# Mako_DSP_Memory_R2_0_-_Copy.net
KiCad netlist of a schematic drawn in Altium Designer
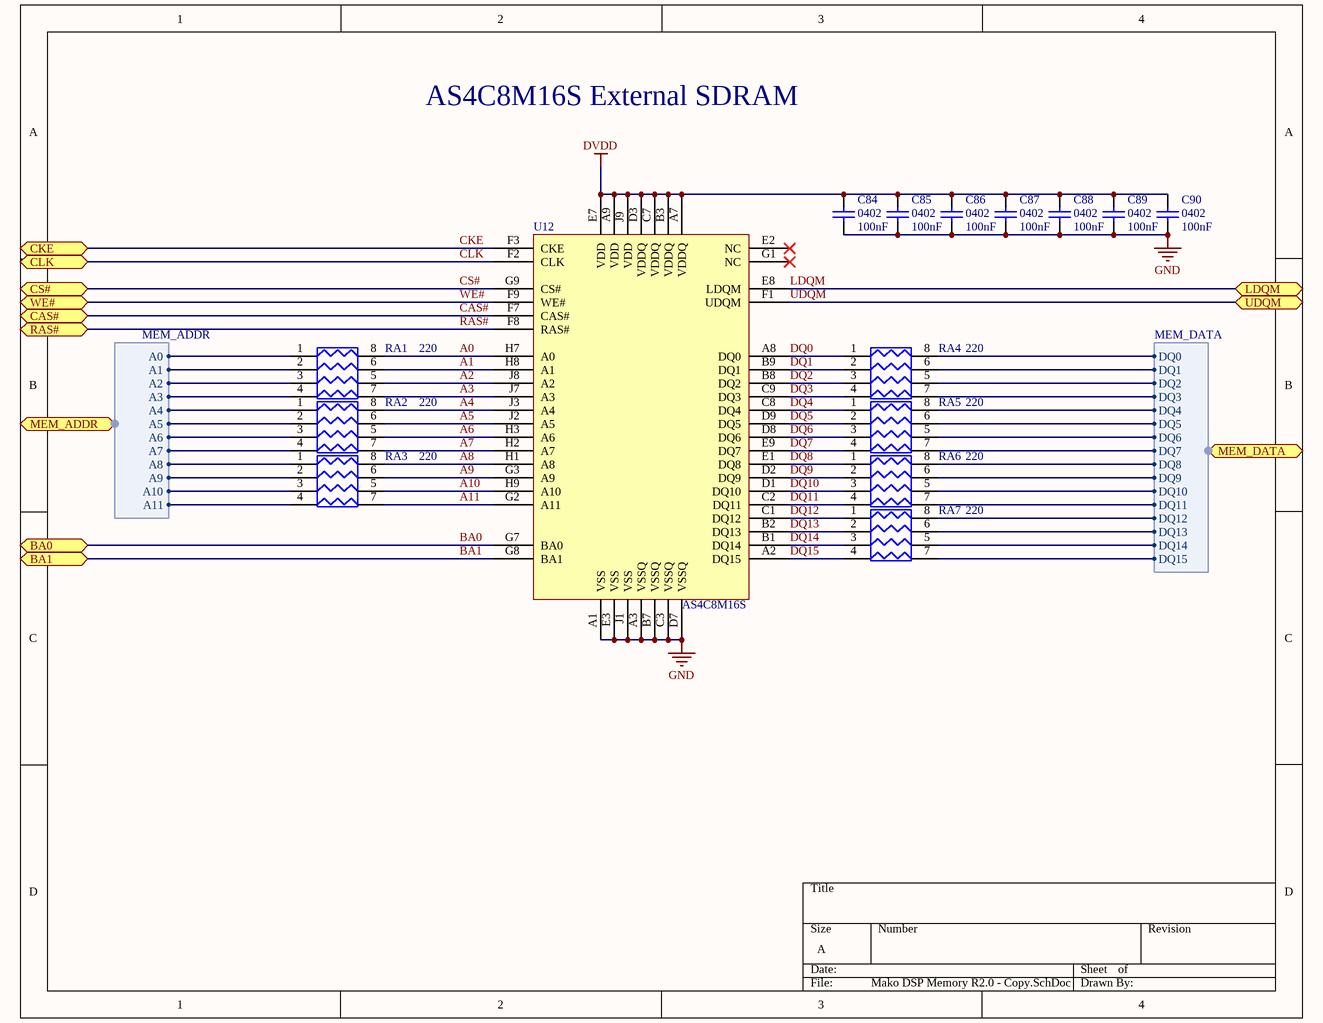
[diagram p0: Mako DSP Memory R2.0 - Copy.SchDoc]

(export (version "E")
  (design (tool "Eeschema 10.0.6"))
  (components
    (comp (ref "C84")
      (value "0402")
      (footprint "0402")
      (description "Capacitor (Semiconductor SIM Model)")
      (fields (field (name "ALTIUM_VALUE") "100nF") (field (name "PUBLISHER") "Altium Limited"))
      (libsource (lib "Miscellaneous Devices") (part "Cap Semi"))
    )
    (comp (ref "C85")
      (value "0402")
      (footprint "0402")
      (description "Capacitor (Semiconductor SIM Model)")
      (fields (field (name "ALTIUM_VALUE") "100nF") (field (name "PUBLISHER") "Altium Limited"))
      (libsource (lib "Miscellaneous Devices") (part "Cap Semi"))
    )
    (comp (ref "C86")
      (value "0402")
      (footprint "0402")
      (description "Capacitor (Semiconductor SIM Model)")
      (fields (field (name "ALTIUM_VALUE") "100nF") (field (name "PUBLISHER") "Altium Limited"))
      (libsource (lib "Miscellaneous Devices") (part "Cap Semi"))
    )
    (comp (ref "C87")
      (value "0402")
      (footprint "0402")
      (description "Capacitor (Semiconductor SIM Model)")
      (fields (field (name "ALTIUM_VALUE") "100nF") (field (name "PUBLISHER") "Altium Limited"))
      (libsource (lib "Miscellaneous Devices") (part "Cap Semi"))
    )
    (comp (ref "C88")
      (value "0402")
      (footprint "0402")
      (description "Capacitor (Semiconductor SIM Model)")
      (fields (field (name "ALTIUM_VALUE") "100nF") (field (name "PUBLISHER") "Altium Limited"))
      (libsource (lib "Miscellaneous Devices") (part "Cap Semi"))
    )
    (comp (ref "C89")
      (value "0402")
      (footprint "0402")
      (description "Capacitor (Semiconductor SIM Model)")
      (fields (field (name "ALTIUM_VALUE") "100nF") (field (name "PUBLISHER") "Altium Limited"))
      (libsource (lib "Miscellaneous Devices") (part "Cap Semi"))
    )
    (comp (ref "C90")
      (value "0402")
      (footprint "0402")
      (description "Capacitor (Semiconductor SIM Model)")
      (fields (field (name "ALTIUM_VALUE") "100nF") (field (name "PUBLISHER") "Altium Limited"))
      (libsource (lib "Miscellaneous Devices") (part "Cap Semi"))
    )
    (comp (ref "RA1")
      (value "220")
      (footprint "742C083")
      (description "Resistor array")
      (fields (field (name "Comment") "RESISTOR ARRAY"))
      (libsource (lib "Mako DSP Schematic Library") (part "RESISTOR ARRAY"))
    )
    (comp (ref "RA2")
      (value "220")
      (footprint "742C083")
      (description "Resistor array")
      (fields (field (name "Comment") "RESISTOR ARRAY"))
      (libsource (lib "Mako DSP Schematic Library") (part "RESISTOR ARRAY"))
    )
    (comp (ref "RA3")
      (value "220")
      (footprint "742C083")
      (description "Resistor array")
      (fields (field (name "Comment") "RESISTOR ARRAY"))
      (libsource (lib "Mako DSP Schematic Library") (part "RESISTOR ARRAY"))
    )
    (comp (ref "RA4")
      (value "220")
      (footprint "742C083")
      (description "Resistor array")
      (fields (field (name "Comment") "RESISTOR ARRAY"))
      (libsource (lib "Mako DSP Schematic Library") (part "RESISTOR ARRAY"))
    )
    (comp (ref "RA5")
      (value "220")
      (footprint "742C083")
      (description "Resistor array")
      (fields (field (name "Comment") "RESISTOR ARRAY"))
      (libsource (lib "Mako DSP Schematic Library") (part "RESISTOR ARRAY"))
    )
    (comp (ref "RA6")
      (value "220")
      (footprint "742C083")
      (description "Resistor array")
      (fields (field (name "Comment") "RESISTOR ARRAY"))
      (libsource (lib "Mako DSP Schematic Library") (part "RESISTOR ARRAY"))
    )
    (comp (ref "RA7")
      (value "220")
      (footprint "742C083")
      (description "Resistor array")
      (fields (field (name "Comment") "RESISTOR ARRAY"))
      (libsource (lib "Mako DSP Schematic Library") (part "RESISTOR ARRAY"))
    )
    (comp (ref "U12")
      (value "AS4C8M16S")
      (footprint "AS4C8M16S")
      (libsource (lib "Mako DSP Schematic Library") (part "AS4C8M16S"))
    )
  )
  (nets
    (net (code "3") (name "/A0") (class "Default")
      (node (ref "RA1") (pin "8") (pinfunction "8_8") (pintype "passive"))
      (node (ref "U12") (pin "H7") (pinfunction "A0_H7") (pintype "passive"))
    )
    (net (code "4") (name "/A1") (class "Default")
      (node (ref "RA1") (pin "6") (pinfunction "6_6") (pintype "passive"))
      (node (ref "U12") (pin "H8") (pinfunction "A1_H8") (pintype "passive"))
    )
    (net (code "5") (name "/A2") (class "Default")
      (node (ref "RA1") (pin "5") (pinfunction "5_5") (pintype "passive"))
      (node (ref "U12") (pin "J8") (pinfunction "A2_J8") (pintype "passive"))
    )
    (net (code "6") (name "/A3") (class "Default")
      (node (ref "RA1") (pin "7") (pinfunction "7_7") (pintype "passive"))
      (node (ref "U12") (pin "J7") (pinfunction "A3_J7") (pintype "passive"))
    )
    (net (code "7") (name "/A4") (class "Default")
      (node (ref "RA2") (pin "8") (pinfunction "8_8") (pintype "passive"))
      (node (ref "U12") (pin "J3") (pinfunction "A4_J3") (pintype "passive"))
    )
    (net (code "8") (name "/A5") (class "Default")
      (node (ref "RA2") (pin "6") (pinfunction "6_6") (pintype "passive"))
      (node (ref "U12") (pin "J2") (pinfunction "A5_J2") (pintype "passive"))
    )
    (net (code "9") (name "/A6") (class "Default")
      (node (ref "RA2") (pin "5") (pinfunction "5_5") (pintype "passive"))
      (node (ref "U12") (pin "H3") (pinfunction "A6_H3") (pintype "passive"))
    )
    (net (code "10") (name "/A7") (class "Default")
      (node (ref "RA2") (pin "7") (pinfunction "7_7") (pintype "passive"))
      (node (ref "U12") (pin "H2") (pinfunction "A7_H2") (pintype "passive"))
    )
    (net (code "11") (name "/A8") (class "Default")
      (node (ref "RA3") (pin "8") (pinfunction "8_8") (pintype "passive"))
      (node (ref "U12") (pin "H1") (pinfunction "A8_H1") (pintype "passive"))
    )
    (net (code "12") (name "/A9") (class "Default")
      (node (ref "RA3") (pin "6") (pinfunction "6_6") (pintype "passive"))
      (node (ref "U12") (pin "G3") (pinfunction "A9_G3") (pintype "passive"))
    )
    (net (code "13") (name "/A10") (class "Default")
      (node (ref "RA3") (pin "5") (pinfunction "5_5") (pintype "passive"))
      (node (ref "U12") (pin "H9") (pinfunction "A10_H9") (pintype "passive"))
    )
    (net (code "14") (name "/A11") (class "Default")
      (node (ref "RA3") (pin "7") (pinfunction "7_7") (pintype "passive"))
      (node (ref "U12") (pin "G2") (pinfunction "A11_G2") (pintype "passive"))
    )
    (net (code "15") (name "/BA0") (class "Default")
      (node (ref "U12") (pin "G7") (pinfunction "BA0_G7") (pintype "passive"))
    )
    (net (code "16") (name "/BA1") (class "Default")
      (node (ref "U12") (pin "G8") (pinfunction "BA1_G8") (pintype "passive"))
    )
    (net (code "17") (name "/CAS#") (class "Default")
      (node (ref "U12") (pin "F7") (pinfunction "CAS#_F7") (pintype "passive"))
    )
    (net (code "18") (name "/CKE") (class "Default")
      (node (ref "U12") (pin "F3") (pinfunction "CKE_F3") (pintype "passive"))
    )
    (net (code "19") (name "/CLK") (class "Default")
      (node (ref "U12") (pin "F2") (pinfunction "CLK_F2") (pintype "passive"))
    )
    (net (code "20") (name "/CS#") (class "Default")
      (node (ref "U12") (pin "G9") (pinfunction "CS#_G9") (pintype "passive"))
    )
    (net (code "21") (name "/DQ0") (class "Default")
      (node (ref "RA4") (pin "1") (pinfunction "1_1") (pintype "passive"))
      (node (ref "U12") (pin "A8") (pinfunction "DQ0_A8") (pintype "passive"))
    )
    (net (code "22") (name "/DQ1") (class "Default")
      (node (ref "RA4") (pin "2") (pinfunction "2_2") (pintype "passive"))
      (node (ref "U12") (pin "B9") (pinfunction "DQ1_B9") (pintype "passive"))
    )
    (net (code "23") (name "/DQ2") (class "Default")
      (node (ref "RA4") (pin "3") (pinfunction "3_3") (pintype "passive"))
      (node (ref "U12") (pin "B8") (pinfunction "DQ2_B8") (pintype "passive"))
    )
    (net (code "24") (name "/DQ3") (class "Default")
      (node (ref "RA4") (pin "4") (pinfunction "4_4") (pintype "passive"))
      (node (ref "U12") (pin "C9") (pinfunction "DQ3_C9") (pintype "passive"))
    )
    (net (code "25") (name "/DQ4") (class "Default")
      (node (ref "RA5") (pin "1") (pinfunction "1_1") (pintype "passive"))
      (node (ref "U12") (pin "C8") (pinfunction "DQ4_C8") (pintype "passive"))
    )
    (net (code "26") (name "/DQ5") (class "Default")
      (node (ref "RA5") (pin "2") (pinfunction "2_2") (pintype "passive"))
      (node (ref "U12") (pin "D9") (pinfunction "DQ5_D9") (pintype "passive"))
    )
    (net (code "27") (name "/DQ6") (class "Default")
      (node (ref "RA5") (pin "3") (pinfunction "3_3") (pintype "passive"))
      (node (ref "U12") (pin "D8") (pinfunction "DQ6_D8") (pintype "passive"))
    )
    (net (code "28") (name "/DQ7") (class "Default")
      (node (ref "RA5") (pin "4") (pinfunction "4_4") (pintype "passive"))
      (node (ref "U12") (pin "E9") (pinfunction "DQ7_E9") (pintype "passive"))
    )
    (net (code "29") (name "/DQ8") (class "Default")
      (node (ref "RA6") (pin "1") (pinfunction "1_1") (pintype "passive"))
      (node (ref "U12") (pin "E1") (pinfunction "DQ8_E1") (pintype "passive"))
    )
    (net (code "30") (name "/DQ9") (class "Default")
      (node (ref "RA6") (pin "2") (pinfunction "2_2") (pintype "passive"))
      (node (ref "U12") (pin "D2") (pinfunction "DQ9_D2") (pintype "passive"))
    )
    (net (code "31") (name "/DQ10") (class "Default")
      (node (ref "RA6") (pin "3") (pinfunction "3_3") (pintype "passive"))
      (node (ref "U12") (pin "D1") (pinfunction "DQ10_D1") (pintype "passive"))
    )
    (net (code "32") (name "/DQ11") (class "Default")
      (node (ref "RA6") (pin "4") (pinfunction "4_4") (pintype "passive"))
      (node (ref "U12") (pin "C2") (pinfunction "DQ11_C2") (pintype "passive"))
    )
    (net (code "33") (name "/DQ12") (class "Default")
      (node (ref "RA7") (pin "1") (pinfunction "1_1") (pintype "passive"))
      (node (ref "U12") (pin "C1") (pinfunction "DQ12_C1") (pintype "passive"))
    )
    (net (code "34") (name "/DQ13") (class "Default")
      (node (ref "RA7") (pin "2") (pinfunction "2_2") (pintype "passive"))
      (node (ref "U12") (pin "B2") (pinfunction "DQ13_B2") (pintype "passive"))
    )
    (net (code "35") (name "/DQ14") (class "Default")
      (node (ref "RA7") (pin "3") (pinfunction "3_3") (pintype "passive"))
      (node (ref "U12") (pin "B1") (pinfunction "DQ14_B1") (pintype "passive"))
    )
    (net (code "36") (name "/DQ15") (class "Default")
      (node (ref "RA7") (pin "4") (pinfunction "4_4") (pintype "passive"))
      (node (ref "U12") (pin "A2") (pinfunction "DQ15_A2") (pintype "passive"))
    )
    (net (code "37") (name "/LDQM") (class "Default")
      (node (ref "U12") (pin "E8") (pinfunction "LDQM_E8") (pintype "passive"))
    )
    (net (code "38") (name "/RAS#") (class "Default")
      (node (ref "U12") (pin "F8") (pinfunction "RAS#_F8") (pintype "passive"))
    )
    (net (code "39") (name "/UDQM") (class "Default")
      (node (ref "U12") (pin "F1") (pinfunction "UDQM_F1") (pintype "passive"))
    )
    (net (code "40") (name "/WE#") (class "Default")
      (node (ref "U12") (pin "F9") (pinfunction "WE#_F9") (pintype "passive"))
    )
    (net (code "43") (name "DVDD") (class "Default")
      (node (ref "C84") (pin "2") (pinfunction "2_2") (pintype "passive"))
      (node (ref "C85") (pin "2") (pinfunction "2_2") (pintype "passive"))
      (node (ref "C86") (pin "2") (pinfunction "2_2") (pintype "passive"))
      (node (ref "C87") (pin "2") (pinfunction "2_2") (pintype "passive"))
      (node (ref "C88") (pin "2") (pinfunction "2_2") (pintype "passive"))
      (node (ref "C89") (pin "2") (pinfunction "2_2") (pintype "passive"))
      (node (ref "C90") (pin "2") (pinfunction "2_2") (pintype "passive"))
      (node (ref "U12") (pin "A7") (pinfunction "VDDQ_A7") (pintype "passive"))
      (node (ref "U12") (pin "A9") (pinfunction "VDD_A9") (pintype "passive"))
      (node (ref "U12") (pin "B3") (pinfunction "VDDQ_B3") (pintype "passive"))
      (node (ref "U12") (pin "C7") (pinfunction "VDDQ_C7") (pintype "passive"))
      (node (ref "U12") (pin "D3") (pinfunction "VDDQ_D3") (pintype "passive"))
      (node (ref "U12") (pin "E7") (pinfunction "VDD_E7") (pintype "passive"))
      (node (ref "U12") (pin "J9") (pinfunction "VDD_J9") (pintype "passive"))
    )
    (net (code "44") (name "GND") (class "Default")
      (node (ref "C84") (pin "1") (pinfunction "1_1") (pintype "passive"))
      (node (ref "C85") (pin "1") (pinfunction "1_1") (pintype "passive"))
      (node (ref "C86") (pin "1") (pinfunction "1_1") (pintype "passive"))
      (node (ref "C87") (pin "1") (pinfunction "1_1") (pintype "passive"))
      (node (ref "C88") (pin "1") (pinfunction "1_1") (pintype "passive"))
      (node (ref "C89") (pin "1") (pinfunction "1_1") (pintype "passive"))
      (node (ref "C90") (pin "1") (pinfunction "1_1") (pintype "passive"))
      (node (ref "U12") (pin "A1") (pinfunction "VSS_A1") (pintype "passive"))
      (node (ref "U12") (pin "A3") (pinfunction "VSSQ_A3") (pintype "passive"))
      (node (ref "U12") (pin "B7") (pinfunction "VSSQ_B7") (pintype "passive"))
      (node (ref "U12") (pin "C3") (pinfunction "VSSQ_C3") (pintype "passive"))
      (node (ref "U12") (pin "D7") (pinfunction "VSSQ_D7") (pintype "passive"))
      (node (ref "U12") (pin "E3") (pinfunction "VSS_E3") (pintype "passive"))
      (node (ref "U12") (pin "J1") (pinfunction "VSS_J1") (pintype "passive"))
    )
    (net (code "45") (name "unconnected-(RA1-Pad1)") (class "Default")
      (node (ref "RA1") (pin "1") (pinfunction "1_1") (pintype "passive"))
    )
    (net (code "46") (name "unconnected-(RA1-Pad2)") (class "Default")
      (node (ref "RA1") (pin "2") (pinfunction "2_2") (pintype "passive"))
    )
    (net (code "47") (name "unconnected-(RA1-Pad3)") (class "Default")
      (node (ref "RA1") (pin "3") (pinfunction "3_3") (pintype "passive"))
    )
    (net (code "48") (name "unconnected-(RA1-Pad4)") (class "Default")
      (node (ref "RA1") (pin "4") (pinfunction "4_4") (pintype "passive"))
    )
    (net (code "49") (name "unconnected-(RA2-Pad1)") (class "Default")
      (node (ref "RA2") (pin "1") (pinfunction "1_1") (pintype "passive"))
    )
    (net (code "50") (name "unconnected-(RA2-Pad2)") (class "Default")
      (node (ref "RA2") (pin "2") (pinfunction "2_2") (pintype "passive"))
    )
    (net (code "51") (name "unconnected-(RA2-Pad3)") (class "Default")
      (node (ref "RA2") (pin "3") (pinfunction "3_3") (pintype "passive"))
    )
    (net (code "52") (name "unconnected-(RA2-Pad4)") (class "Default")
      (node (ref "RA2") (pin "4") (pinfunction "4_4") (pintype "passive"))
    )
    (net (code "53") (name "unconnected-(RA3-Pad1)") (class "Default")
      (node (ref "RA3") (pin "1") (pinfunction "1_1") (pintype "passive"))
    )
    (net (code "54") (name "unconnected-(RA3-Pad2)") (class "Default")
      (node (ref "RA3") (pin "2") (pinfunction "2_2") (pintype "passive"))
    )
    (net (code "55") (name "unconnected-(RA3-Pad3)") (class "Default")
      (node (ref "RA3") (pin "3") (pinfunction "3_3") (pintype "passive"))
    )
    (net (code "56") (name "unconnected-(RA3-Pad4)") (class "Default")
      (node (ref "RA3") (pin "4") (pinfunction "4_4") (pintype "passive"))
    )
    (net (code "57") (name "unconnected-(RA4-Pad5)") (class "Default")
      (node (ref "RA4") (pin "5") (pinfunction "5_5") (pintype "passive"))
    )
    (net (code "58") (name "unconnected-(RA4-Pad6)") (class "Default")
      (node (ref "RA4") (pin "6") (pinfunction "6_6") (pintype "passive"))
    )
    (net (code "59") (name "unconnected-(RA4-Pad7)") (class "Default")
      (node (ref "RA4") (pin "7") (pinfunction "7_7") (pintype "passive"))
    )
    (net (code "60") (name "unconnected-(RA4-Pad8)") (class "Default")
      (node (ref "RA4") (pin "8") (pinfunction "8_8") (pintype "passive"))
    )
    (net (code "61") (name "unconnected-(RA5-Pad5)") (class "Default")
      (node (ref "RA5") (pin "5") (pinfunction "5_5") (pintype "passive"))
    )
    (net (code "62") (name "unconnected-(RA5-Pad6)") (class "Default")
      (node (ref "RA5") (pin "6") (pinfunction "6_6") (pintype "passive"))
    )
    (net (code "63") (name "unconnected-(RA5-Pad7)") (class "Default")
      (node (ref "RA5") (pin "7") (pinfunction "7_7") (pintype "passive"))
    )
    (net (code "64") (name "unconnected-(RA5-Pad8)") (class "Default")
      (node (ref "RA5") (pin "8") (pinfunction "8_8") (pintype "passive"))
    )
    (net (code "65") (name "unconnected-(RA6-Pad5)") (class "Default")
      (node (ref "RA6") (pin "5") (pinfunction "5_5") (pintype "passive"))
    )
    (net (code "66") (name "unconnected-(RA6-Pad6)") (class "Default")
      (node (ref "RA6") (pin "6") (pinfunction "6_6") (pintype "passive"))
    )
    (net (code "67") (name "unconnected-(RA6-Pad7)") (class "Default")
      (node (ref "RA6") (pin "7") (pinfunction "7_7") (pintype "passive"))
    )
    (net (code "68") (name "unconnected-(RA6-Pad8)") (class "Default")
      (node (ref "RA6") (pin "8") (pinfunction "8_8") (pintype "passive"))
    )
    (net (code "69") (name "unconnected-(RA7-Pad5)") (class "Default")
      (node (ref "RA7") (pin "5") (pinfunction "5_5") (pintype "passive"))
    )
    (net (code "70") (name "unconnected-(RA7-Pad6)") (class "Default")
      (node (ref "RA7") (pin "6") (pinfunction "6_6") (pintype "passive"))
    )
    (net (code "71") (name "unconnected-(RA7-Pad7)") (class "Default")
      (node (ref "RA7") (pin "7") (pinfunction "7_7") (pintype "passive"))
    )
    (net (code "72") (name "unconnected-(RA7-Pad8)") (class "Default")
      (node (ref "RA7") (pin "8") (pinfunction "8_8") (pintype "passive"))
    )
    (net (code "73") (name "unconnected-(U12-NC-PadE2)") (class "Default")
      (node (ref "U12") (pin "E2") (pinfunction "NC_E2") (pintype "passive+no_connect"))
    )
    (net (code "74") (name "unconnected-(U12-NC-PadG1)") (class "Default")
      (node (ref "U12") (pin "G1") (pinfunction "NC_G1") (pintype "passive+no_connect"))
    )
  )
)
